# CW340_STATUS_LEDs.net
KiCad netlist of a schematic drawn in Altium Designer
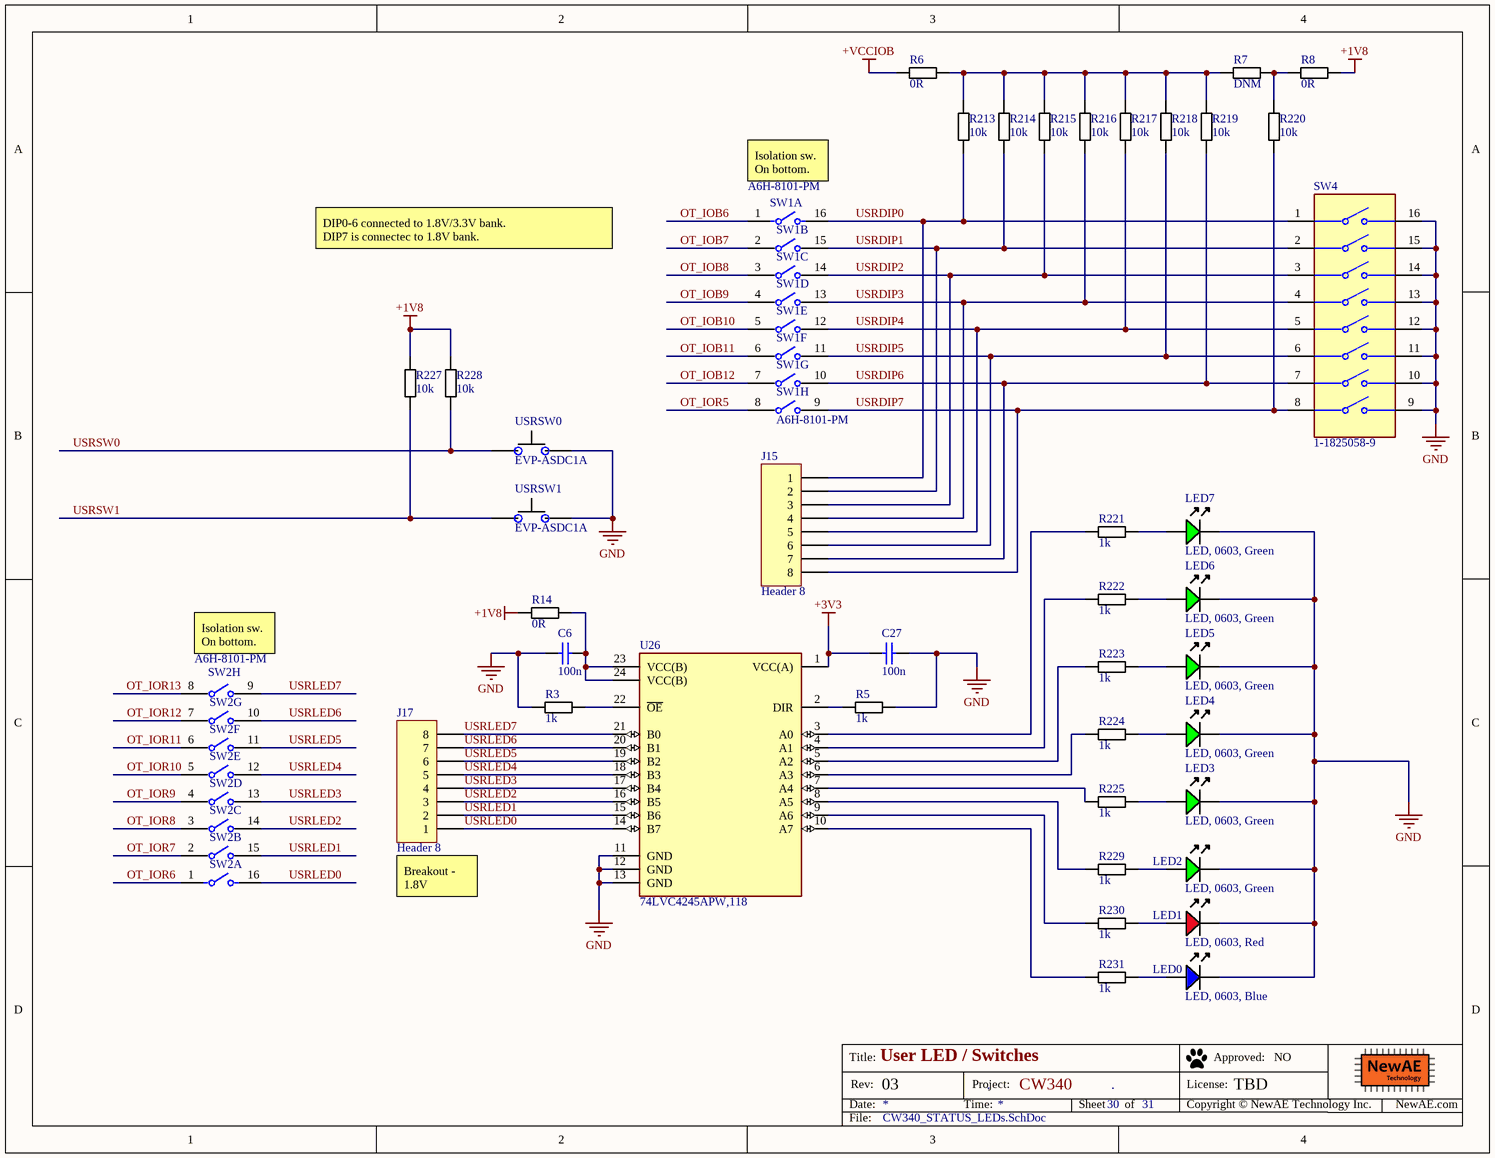
[diagram p0: CW340_STATUS_LEDs.SchDoc]

(export (version "E")
  (design (tool "Eeschema 10.0.6"))
  (components
    (comp (ref "C6")
      (value "100n")
      (footprint "CAPC0402_M")
      (description "100n, 0402")
      (fields (field (name "PART NUMBER") "CCHIP-100n-0402"))
      (libsource (lib "NewAE_AltiumLib") (part "CAP"))
    )
    (comp (ref "C27")
      (value "100n")
      (footprint "CAPC0402_M")
      (description "100n, 0402")
      (fields (field (name "PART NUMBER") "CCHIP-100n-0402"))
      (libsource (lib "NewAE_AltiumLib") (part "CAP"))
    )
    (comp (ref "J15")
      (value "Header 8")
      (footprint "HDR1X8")
      (description "Header, 8-Pin")
      (fields (field (name "PUBLISHER") "Altium Limited"))
      (libsource (lib "Miscellaneous Connectors") (part "Header 8"))
    )
    (comp (ref "J17")
      (value "Header 8")
      (footprint "HDR1X8")
      (description "Header, 8-Pin")
      (fields (field (name "PUBLISHER") "Altium Limited"))
      (libsource (lib "") (part "Header 8_1"))
    )
    (comp (ref "LED0")
      (value "LED, 0603, Blue")
      (footprint "LED-0603-BLUE")
      (description "Chip LED, Blue")
      (fields (field (name "PART NUMBER") "LEDCHIP_0603_BLUE"))
      (libsource (lib "NewAE_AltiumLib") (part "LED_BLUE"))
    )
    (comp (ref "LED1")
      (value "LED, 0603, Red")
      (footprint "LED-0603-RED")
      (description "Chip LED, Red")
      (fields (field (name "PART NUMBER") "LEDCHIP_0603_RED"))
      (libsource (lib "NewAE_AltiumLib") (part "LED_RED"))
    )
    (comp (ref "LED2")
      (value "LED, 0603, Green")
      (footprint "LED-0603-GREEN")
      (description "Chip LED, Green")
      (fields (field (name "PART NUMBER") "LEDCHIP_0603_GREEN"))
      (libsource (lib "NewAE_AltiumLib") (part "LED_GREEN"))
    )
    (comp (ref "LED3")
      (value "LED, 0603, Green")
      (footprint "LED-0603-GREEN")
      (description "Chip LED, Green")
      (fields (field (name "PART NUMBER") "LEDCHIP_0603_GREEN"))
      (libsource (lib "NewAE_AltiumLib") (part "LED_GREEN"))
    )
    (comp (ref "LED4")
      (value "LED, 0603, Green")
      (footprint "LED-0603-GREEN")
      (description "Chip LED, Green")
      (fields (field (name "PART NUMBER") "LEDCHIP_0603_GREEN"))
      (libsource (lib "NewAE_AltiumLib") (part "LED_GREEN"))
    )
    (comp (ref "LED5")
      (value "LED, 0603, Green")
      (footprint "LED-0603-GREEN")
      (description "Chip LED, Green")
      (fields (field (name "PART NUMBER") "LEDCHIP_0603_GREEN"))
      (libsource (lib "NewAE_AltiumLib") (part "LED_GREEN"))
    )
    (comp (ref "LED6")
      (value "LED, 0603, Green")
      (footprint "LED-0603-GREEN")
      (description "Chip LED, Green")
      (fields (field (name "PART NUMBER") "LEDCHIP_0603_GREEN"))
      (libsource (lib "NewAE_AltiumLib") (part "LED_GREEN"))
    )
    (comp (ref "LED7")
      (value "LED, 0603, Green")
      (footprint "LED-0603-GREEN")
      (description "Chip LED, Green")
      (fields (field (name "PART NUMBER") "LEDCHIP_0603_GREEN"))
      (libsource (lib "NewAE_AltiumLib") (part "LED_GREEN"))
    )
    (comp (ref "R3")
      (value "1k")
      (footprint "RESC1005X40N")
      (description "1k res, 0402, 1%, 1/16W")
      (fields (field (name "PART NUMBER") "RCHIP-1K-0402") (field (name "TOLERANCE") "1%"))
      (libsource (lib "NewAE_AltiumLib") (part "RES-EU"))
    )
    (comp (ref "R5")
      (value "1k")
      (footprint "RESC1005X40N")
      (description "1k res, 0402, 1%, 1/16W")
      (fields (field (name "PART NUMBER") "RCHIP-1K-0402") (field (name "TOLERANCE") "1%"))
      (libsource (lib "NewAE_AltiumLib") (part "RES-EU"))
    )
    (comp (ref "R6")
      (value "0R")
      (footprint "RESC1005X40N")
      (fields (field (name "PART NUMBER") "RCHIP-0R-0402"))
      (libsource (lib "NewAE_AltiumLib") (part "RES-EU"))
    )
    (comp (ref "R7")
      (value "DNM")
      (footprint "RESC1005X40N")
      (fields (field (name "PART NUMBER") "RCHIP-DNM-0402"))
      (libsource (lib "NewAE_AltiumLib") (part "RES-EU"))
    )
    (comp (ref "R8")
      (value "0R")
      (footprint "RESC1005X40N")
      (fields (field (name "PART NUMBER") "RCHIP-0R-0402"))
      (libsource (lib "NewAE_AltiumLib") (part "RES-EU"))
    )
    (comp (ref "R14")
      (value "0R")
      (footprint "RESC1005X40N")
      (fields (field (name "PART NUMBER") "RCHIP-0R-0402"))
      (libsource (lib "NewAE_AltiumLib") (part "RES-EU"))
    )
    (comp (ref "R213")
      (value "10k")
      (footprint "RESC1005X40N")
      (description "10k res, 0402, 1%, 1/16W")
      (fields (field (name "PART NUMBER") "RCHIP-10K-0402") (field (name "TOLERANCE") "1%"))
      (libsource (lib "") (part "RES-EU_1"))
    )
    (comp (ref "R214")
      (value "10k")
      (footprint "RESC1005X40N")
      (description "10k res, 0402, 1%, 1/16W")
      (fields (field (name "PART NUMBER") "RCHIP-10K-0402") (field (name "TOLERANCE") "1%"))
      (libsource (lib "") (part "RES-EU_1"))
    )
    (comp (ref "R215")
      (value "10k")
      (footprint "RESC1005X40N")
      (description "10k res, 0402, 1%, 1/16W")
      (fields (field (name "PART NUMBER") "RCHIP-10K-0402") (field (name "TOLERANCE") "1%"))
      (libsource (lib "") (part "RES-EU_1"))
    )
    (comp (ref "R216")
      (value "10k")
      (footprint "RESC1005X40N")
      (description "10k res, 0402, 1%, 1/16W")
      (fields (field (name "PART NUMBER") "RCHIP-10K-0402") (field (name "TOLERANCE") "1%"))
      (libsource (lib "") (part "RES-EU_1"))
    )
    (comp (ref "R217")
      (value "10k")
      (footprint "RESC1005X40N")
      (description "10k res, 0402, 1%, 1/16W")
      (fields (field (name "PART NUMBER") "RCHIP-10K-0402") (field (name "TOLERANCE") "1%"))
      (libsource (lib "") (part "RES-EU_1"))
    )
    (comp (ref "R218")
      (value "10k")
      (footprint "RESC1005X40N")
      (description "10k res, 0402, 1%, 1/16W")
      (fields (field (name "PART NUMBER") "RCHIP-10K-0402") (field (name "TOLERANCE") "1%"))
      (libsource (lib "") (part "RES-EU_1"))
    )
    (comp (ref "R219")
      (value "10k")
      (footprint "RESC1005X40N")
      (description "10k res, 0402, 1%, 1/16W")
      (fields (field (name "PART NUMBER") "RCHIP-10K-0402") (field (name "TOLERANCE") "1%"))
      (libsource (lib "") (part "RES-EU_1"))
    )
    (comp (ref "R220")
      (value "10k")
      (footprint "RESC1005X40N")
      (description "10k res, 0402, 1%, 1/16W")
      (fields (field (name "PART NUMBER") "RCHIP-10K-0402") (field (name "TOLERANCE") "1%"))
      (libsource (lib "") (part "RES-EU_1"))
    )
    (comp (ref "R221")
      (value "1k")
      (footprint "RESC1005X40N")
      (description "1k res, 0402, 1%, 1/16W")
      (fields (field (name "PART NUMBER") "RCHIP-1K-0402") (field (name "TOLERANCE") "1%"))
      (libsource (lib "NewAE_AltiumLib") (part "RES-EU"))
    )
    (comp (ref "R222")
      (value "1k")
      (footprint "RESC1005X40N")
      (description "1k res, 0402, 1%, 1/16W")
      (fields (field (name "PART NUMBER") "RCHIP-1K-0402") (field (name "TOLERANCE") "1%"))
      (libsource (lib "NewAE_AltiumLib") (part "RES-EU"))
    )
    (comp (ref "R223")
      (value "1k")
      (footprint "RESC1005X40N")
      (description "1k res, 0402, 1%, 1/16W")
      (fields (field (name "PART NUMBER") "RCHIP-1K-0402") (field (name "TOLERANCE") "1%"))
      (libsource (lib "NewAE_AltiumLib") (part "RES-EU"))
    )
    (comp (ref "R224")
      (value "1k")
      (footprint "RESC1005X40N")
      (description "1k res, 0402, 1%, 1/16W")
      (fields (field (name "PART NUMBER") "RCHIP-1K-0402") (field (name "TOLERANCE") "1%"))
      (libsource (lib "NewAE_AltiumLib") (part "RES-EU"))
    )
    (comp (ref "R225")
      (value "1k")
      (footprint "RESC1005X40N")
      (description "1k res, 0402, 1%, 1/16W")
      (fields (field (name "PART NUMBER") "RCHIP-1K-0402") (field (name "TOLERANCE") "1%"))
      (libsource (lib "NewAE_AltiumLib") (part "RES-EU"))
    )
    (comp (ref "R227")
      (value "10k")
      (footprint "RESC1005X40N")
      (description "10k res, 0402, 1%, 1/16W")
      (fields (field (name "PART NUMBER") "RCHIP-10K-0402") (field (name "TOLERANCE") "1%"))
      (libsource (lib "") (part "RES-EU_1"))
    )
    (comp (ref "R228")
      (value "10k")
      (footprint "RESC1005X40N")
      (description "10k res, 0402, 1%, 1/16W")
      (fields (field (name "PART NUMBER") "RCHIP-10K-0402") (field (name "TOLERANCE") "1%"))
      (libsource (lib "") (part "RES-EU_1"))
    )
    (comp (ref "R229")
      (value "1k")
      (footprint "RESC1005X40N")
      (description "1k res, 0402, 1%, 1/16W")
      (fields (field (name "PART NUMBER") "RCHIP-1K-0402") (field (name "TOLERANCE") "1%"))
      (libsource (lib "NewAE_AltiumLib") (part "RES-EU"))
    )
    (comp (ref "R230")
      (value "1k")
      (footprint "RESC1005X40N")
      (description "1k res, 0402, 1%, 1/16W")
      (fields (field (name "PART NUMBER") "RCHIP-1K-0402") (field (name "TOLERANCE") "1%"))
      (libsource (lib "NewAE_AltiumLib") (part "RES-EU"))
    )
    (comp (ref "R231")
      (value "1k")
      (footprint "RESC1005X40N")
      (description "1k res, 0402, 1%, 1/16W")
      (fields (field (name "PART NUMBER") "RCHIP-1K-0402") (field (name "TOLERANCE") "1%"))
      (libsource (lib "NewAE_AltiumLib") (part "RES-EU"))
    )
    (comp (ref "SW1")
      (value "A6H-8101-PM")
      (footprint "FP-A6H-8101-PM-MFG")
      (description "SWITCH SLIDE DIP SPST 25MA 24V")
      (libsource (lib "Altium Content Vault") (part "b1c630a2f26d6f55c46b66680387f8a"))
    )
    (comp (ref "SW2")
      (value "A6H-8101-PM")
      (footprint "FP-A6H-8101-PM-MFG")
      (description "SWITCH SLIDE DIP SPST 25MA 24V")
      (libsource (lib "Altium Content Vault") (part "b1c630a2f26d6f55c46b66680387f8a"))
    )
    (comp (ref "SW4")
      (value "1-1825058-9")
      (footprint "FP-1-1825058-9-MFG")
      (description "SWITCH SLIDE DIP SPST 100MA 24V")
      (fields
        (field (name "MANUFACTURER") "TE Connectivity")
        (field (name "OCTOPART") "https://octopart.com/1-1825058-9-te+connectivity-46507285")
      )
      (libsource (lib "Altium Content Vault") (part "88b473189f0daa5e8e83a09a3141fee"))
    )
    (comp (ref "U26")
      (value "74LVC4245APW,118")
      (footprint "FP-SOT355-1-MFG")
      (description "IC TRNSLTR BIDIRECTIONAL 24TSSOP")
      (libsource (lib "Altium Content Vault") (part "891e07fab61dc967ea688c1a07de794"))
    )
    (comp (ref "USRSW0")
      (value "EVP-ASDC1A")
      (footprint "EVPAS")
      (description "Pushbutton, SMD, 2.5NM force, NO")
      (libsource (lib "NewAE_AltiumLib") (part "SW_PB_NO_2PIN"))
    )
    (comp (ref "USRSW1")
      (value "EVP-ASDC1A")
      (footprint "EVPAS")
      (description "Pushbutton, SMD, 2.5NM force, NO")
      (libsource (lib "NewAE_AltiumLib") (part "SW_PB_NO_2PIN"))
    )
  )
  (nets
    (net (code "1") (name "+1V8") (class "Default")
      (node (ref "R14") (pin "1") (pinfunction "1_1") (pintype "passive"))
      (node (ref "R227") (pin "1") (pinfunction "1_1") (pintype "passive"))
      (node (ref "R228") (pin "1") (pinfunction "1_1") (pintype "passive"))
      (node (ref "R8") (pin "2") (pinfunction "2_2") (pintype "passive"))
    )
    (net (code "2") (name "+3V3") (class "Default")
      (node (ref "C27") (pin "1") (pinfunction "1_1") (pintype "passive"))
      (node (ref "U26") (pin "1") (pinfunction "VCC(A)_1") (pintype "power_in"))
    )
    (net (code "3") (name "+VCCIOB") (class "Default")
      (node (ref "R6") (pin "1") (pinfunction "1_1") (pintype "passive"))
    )
    (net (code "4") (name "/OT_IOB6") (class "Default")
      (node (ref "SW1") (pin "1") (pinfunction "1_1") (pintype "passive"))
    )
    (net (code "5") (name "/OT_IOB7") (class "Default")
      (node (ref "SW1") (pin "2") (pinfunction "2_2") (pintype "passive"))
    )
    (net (code "6") (name "/OT_IOB8") (class "Default")
      (node (ref "SW1") (pin "3") (pinfunction "3_3") (pintype "passive"))
    )
    (net (code "7") (name "/OT_IOB9") (class "Default")
      (node (ref "SW1") (pin "4") (pinfunction "4_4") (pintype "passive"))
    )
    (net (code "8") (name "/OT_IOB10") (class "Default")
      (node (ref "SW1") (pin "5") (pinfunction "5_5") (pintype "passive"))
    )
    (net (code "9") (name "/OT_IOB11") (class "Default")
      (node (ref "SW1") (pin "6") (pinfunction "6_6") (pintype "passive"))
    )
    (net (code "10") (name "/OT_IOB12") (class "Default")
      (node (ref "SW1") (pin "7") (pinfunction "7_7") (pintype "passive"))
    )
    (net (code "11") (name "/OT_IOR5") (class "Default")
      (node (ref "SW1") (pin "8") (pinfunction "8_8") (pintype "passive"))
    )
    (net (code "12") (name "/OT_IOR6") (class "Default")
      (node (ref "SW2") (pin "1") (pinfunction "1_1") (pintype "passive"))
    )
    (net (code "13") (name "/OT_IOR7") (class "Default")
      (node (ref "SW2") (pin "2") (pinfunction "2_2") (pintype "passive"))
    )
    (net (code "14") (name "/OT_IOR8") (class "Default")
      (node (ref "SW2") (pin "3") (pinfunction "3_3") (pintype "passive"))
    )
    (net (code "15") (name "/OT_IOR9") (class "Default")
      (node (ref "SW2") (pin "4") (pinfunction "4_4") (pintype "passive"))
    )
    (net (code "16") (name "/OT_IOR10") (class "Default")
      (node (ref "SW2") (pin "5") (pinfunction "5_5") (pintype "passive"))
    )
    (net (code "17") (name "/OT_IOR11") (class "Default")
      (node (ref "SW2") (pin "6") (pinfunction "6_6") (pintype "passive"))
    )
    (net (code "18") (name "/OT_IOR12") (class "Default")
      (node (ref "SW2") (pin "7") (pinfunction "7_7") (pintype "passive"))
    )
    (net (code "19") (name "/OT_IOR13") (class "Default")
      (node (ref "SW2") (pin "8") (pinfunction "8_8") (pintype "passive"))
    )
    (net (code "20") (name "/USRDIP0") (class "Default")
      (node (ref "J15") (pin "1") (pinfunction "1_1") (pintype "passive"))
      (node (ref "R213") (pin "2") (pinfunction "2_2") (pintype "passive"))
      (node (ref "SW1") (pin "16") (pinfunction "16_16") (pintype "passive"))
      (node (ref "SW4") (pin "1") (pinfunction "1_1") (pintype "passive"))
    )
    (net (code "21") (name "/USRDIP1") (class "Default")
      (node (ref "J15") (pin "2") (pinfunction "2_2") (pintype "passive"))
      (node (ref "R214") (pin "2") (pinfunction "2_2") (pintype "passive"))
      (node (ref "SW1") (pin "15") (pinfunction "15_15") (pintype "passive"))
      (node (ref "SW4") (pin "2") (pinfunction "2_2") (pintype "passive"))
    )
    (net (code "22") (name "/USRDIP2") (class "Default")
      (node (ref "J15") (pin "3") (pinfunction "3_3") (pintype "passive"))
      (node (ref "R215") (pin "2") (pinfunction "2_2") (pintype "passive"))
      (node (ref "SW1") (pin "14") (pinfunction "14_14") (pintype "passive"))
      (node (ref "SW4") (pin "3") (pinfunction "3_3") (pintype "passive"))
    )
    (net (code "23") (name "/USRDIP3") (class "Default")
      (node (ref "J15") (pin "4") (pinfunction "4_4") (pintype "passive"))
      (node (ref "R216") (pin "2") (pinfunction "2_2") (pintype "passive"))
      (node (ref "SW1") (pin "13") (pinfunction "13_13") (pintype "passive"))
      (node (ref "SW4") (pin "4") (pinfunction "4_4") (pintype "passive"))
    )
    (net (code "24") (name "/USRDIP4") (class "Default")
      (node (ref "J15") (pin "5") (pinfunction "5_5") (pintype "passive"))
      (node (ref "R217") (pin "2") (pinfunction "2_2") (pintype "passive"))
      (node (ref "SW1") (pin "12") (pinfunction "12_12") (pintype "passive"))
      (node (ref "SW4") (pin "5") (pinfunction "5_5") (pintype "passive"))
    )
    (net (code "25") (name "/USRDIP5") (class "Default")
      (node (ref "J15") (pin "6") (pinfunction "6_6") (pintype "passive"))
      (node (ref "R218") (pin "2") (pinfunction "2_2") (pintype "passive"))
      (node (ref "SW1") (pin "11") (pinfunction "11_11") (pintype "passive"))
      (node (ref "SW4") (pin "6") (pinfunction "6_6") (pintype "passive"))
    )
    (net (code "26") (name "/USRDIP6") (class "Default")
      (node (ref "J15") (pin "7") (pinfunction "7_7") (pintype "passive"))
      (node (ref "R219") (pin "2") (pinfunction "2_2") (pintype "passive"))
      (node (ref "SW1") (pin "10") (pinfunction "10_10") (pintype "passive"))
      (node (ref "SW4") (pin "7") (pinfunction "7_7") (pintype "passive"))
    )
    (net (code "27") (name "/USRDIP7") (class "Default")
      (node (ref "J15") (pin "8") (pinfunction "8_8") (pintype "passive"))
      (node (ref "R220") (pin "2") (pinfunction "2_2") (pintype "passive"))
      (node (ref "SW1") (pin "9") (pinfunction "9_9") (pintype "passive"))
      (node (ref "SW4") (pin "8") (pinfunction "8_8") (pintype "passive"))
    )
    (net (code "28") (name "/USRLED0") (class "Default")
      (node (ref "J17") (pin "1") (pinfunction "1_1") (pintype "passive"))
      (node (ref "SW2") (pin "16") (pinfunction "16_16") (pintype "passive"))
      (node (ref "U26") (pin "14") (pinfunction "B7_14") (pintype "bidirectional"))
    )
    (net (code "29") (name "/USRLED1") (class "Default")
      (node (ref "J17") (pin "2") (pinfunction "2_2") (pintype "passive"))
      (node (ref "SW2") (pin "15") (pinfunction "15_15") (pintype "passive"))
      (node (ref "U26") (pin "15") (pinfunction "B6_15") (pintype "bidirectional"))
    )
    (net (code "30") (name "/USRLED2") (class "Default")
      (node (ref "J17") (pin "3") (pinfunction "3_3") (pintype "passive"))
      (node (ref "SW2") (pin "14") (pinfunction "14_14") (pintype "passive"))
      (node (ref "U26") (pin "16") (pinfunction "B5_16") (pintype "bidirectional"))
    )
    (net (code "31") (name "/USRLED3") (class "Default")
      (node (ref "J17") (pin "4") (pinfunction "4_4") (pintype "passive"))
      (node (ref "SW2") (pin "13") (pinfunction "13_13") (pintype "passive"))
      (node (ref "U26") (pin "17") (pinfunction "B4_17") (pintype "bidirectional"))
    )
    (net (code "32") (name "/USRLED4") (class "Default")
      (node (ref "J17") (pin "5") (pinfunction "5_5") (pintype "passive"))
      (node (ref "SW2") (pin "12") (pinfunction "12_12") (pintype "passive"))
      (node (ref "U26") (pin "18") (pinfunction "B3_18") (pintype "bidirectional"))
    )
    (net (code "33") (name "/USRLED5") (class "Default")
      (node (ref "J17") (pin "6") (pinfunction "6_6") (pintype "passive"))
      (node (ref "SW2") (pin "11") (pinfunction "11_11") (pintype "passive"))
      (node (ref "U26") (pin "19") (pinfunction "B2_19") (pintype "bidirectional"))
    )
    (net (code "34") (name "/USRLED6") (class "Default")
      (node (ref "J17") (pin "7") (pinfunction "7_7") (pintype "passive"))
      (node (ref "SW2") (pin "10") (pinfunction "10_10") (pintype "passive"))
      (node (ref "U26") (pin "20") (pinfunction "B1_20") (pintype "bidirectional"))
    )
    (net (code "35") (name "/USRLED7") (class "Default")
      (node (ref "J17") (pin "8") (pinfunction "8_8") (pintype "passive"))
      (node (ref "SW2") (pin "9") (pinfunction "9_9") (pintype "passive"))
      (node (ref "U26") (pin "21") (pinfunction "B0_21") (pintype "bidirectional"))
    )
    (net (code "36") (name "/USRSW0") (class "Default")
      (node (ref "R228") (pin "2") (pinfunction "2_2") (pintype "passive"))
      (node (ref "USRSW0") (pin "1") (pinfunction "IN_1") (pintype "passive"))
    )
    (net (code "37") (name "/USRSW1") (class "Default")
      (node (ref "R227") (pin "2") (pinfunction "2_2") (pintype "passive"))
      (node (ref "USRSW1") (pin "1") (pinfunction "IN_1") (pintype "passive"))
    )
    (net (code "38") (name "GND") (class "Default")
      (node (ref "C27") (pin "2") (pinfunction "2_2") (pintype "passive"))
      (node (ref "C6") (pin "1") (pinfunction "1_1") (pintype "passive"))
      (node (ref "LED0") (pin "K") (pinfunction "K_K") (pintype "passive"))
      (node (ref "LED1") (pin "K") (pinfunction "K_K") (pintype "passive"))
      (node (ref "LED2") (pin "K") (pinfunction "K_K") (pintype "passive"))
      (node (ref "LED3") (pin "K") (pinfunction "K_K") (pintype "passive"))
      (node (ref "LED4") (pin "K") (pinfunction "K_K") (pintype "passive"))
      (node (ref "LED5") (pin "K") (pinfunction "K_K") (pintype "passive"))
      (node (ref "LED6") (pin "K") (pinfunction "K_K") (pintype "passive"))
      (node (ref "LED7") (pin "K") (pinfunction "K_K") (pintype "passive"))
      (node (ref "R3") (pin "1") (pinfunction "1_1") (pintype "passive"))
      (node (ref "R5") (pin "2") (pinfunction "2_2") (pintype "passive"))
      (node (ref "SW4") (pin "10") (pinfunction "10_10") (pintype "passive"))
      (node (ref "SW4") (pin "11") (pinfunction "11_11") (pintype "passive"))
      (node (ref "SW4") (pin "12") (pinfunction "12_12") (pintype "passive"))
      (node (ref "SW4") (pin "13") (pinfunction "13_13") (pintype "passive"))
      (node (ref "SW4") (pin "14") (pinfunction "14_14") (pintype "passive"))
      (node (ref "SW4") (pin "15") (pinfunction "15_15") (pintype "passive"))
      (node (ref "SW4") (pin "16") (pinfunction "16_16") (pintype "passive"))
      (node (ref "SW4") (pin "9") (pinfunction "9_9") (pintype "passive"))
      (node (ref "U26") (pin "11") (pinfunction "GND_11") (pintype "power_in"))
      (node (ref "U26") (pin "12") (pinfunction "GND_12") (pintype "power_in"))
      (node (ref "U26") (pin "13") (pinfunction "GND_13") (pintype "power_in"))
      (node (ref "USRSW0") (pin "2") (pinfunction "IN_2") (pintype "passive"))
      (node (ref "USRSW1") (pin "2") (pinfunction "IN_2") (pintype "passive"))
    )
    (net (code "39") (name "Net-(C6-Pad2)") (class "Default")
      (node (ref "C6") (pin "2") (pinfunction "2_2") (pintype "passive"))
      (node (ref "R14") (pin "2") (pinfunction "2_2") (pintype "passive"))
      (node (ref "U26") (pin "23") (pinfunction "VCC(B)_23") (pintype "power_in"))
      (node (ref "U26") (pin "24") (pinfunction "VCC(B)_24") (pintype "power_in"))
    )
    (net (code "40") (name "Net-(LED0-PadA)") (class "Default")
      (node (ref "LED0") (pin "A") (pinfunction "A_A") (pintype "passive"))
      (node (ref "R231") (pin "2") (pinfunction "2_2") (pintype "passive"))
    )
    (net (code "41") (name "Net-(LED1-PadA)") (class "Default")
      (node (ref "LED1") (pin "A") (pinfunction "A_A") (pintype "passive"))
      (node (ref "R230") (pin "2") (pinfunction "2_2") (pintype "passive"))
    )
    (net (code "42") (name "Net-(LED2-PadA)") (class "Default")
      (node (ref "LED2") (pin "A") (pinfunction "A_A") (pintype "passive"))
      (node (ref "R229") (pin "2") (pinfunction "2_2") (pintype "passive"))
    )
    (net (code "43") (name "Net-(LED3-PadA)") (class "Default")
      (node (ref "LED3") (pin "A") (pinfunction "A_A") (pintype "passive"))
      (node (ref "R225") (pin "2") (pinfunction "2_2") (pintype "passive"))
    )
    (net (code "44") (name "Net-(LED4-PadA)") (class "Default")
      (node (ref "LED4") (pin "A") (pinfunction "A_A") (pintype "passive"))
      (node (ref "R224") (pin "2") (pinfunction "2_2") (pintype "passive"))
    )
    (net (code "45") (name "Net-(LED5-PadA)") (class "Default")
      (node (ref "LED5") (pin "A") (pinfunction "A_A") (pintype "passive"))
      (node (ref "R223") (pin "2") (pinfunction "2_2") (pintype "passive"))
    )
    (net (code "46") (name "Net-(LED6-PadA)") (class "Default")
      (node (ref "LED6") (pin "A") (pinfunction "A_A") (pintype "passive"))
      (node (ref "R222") (pin "2") (pinfunction "2_2") (pintype "passive"))
    )
    (net (code "47") (name "Net-(LED7-PadA)") (class "Default")
      (node (ref "LED7") (pin "A") (pinfunction "A_A") (pintype "passive"))
      (node (ref "R221") (pin "2") (pinfunction "2_2") (pintype "passive"))
    )
    (net (code "48") (name "Net-(R213-Pad1)") (class "Default")
      (node (ref "R213") (pin "1") (pinfunction "1_1") (pintype "passive"))
      (node (ref "R214") (pin "1") (pinfunction "1_1") (pintype "passive"))
      (node (ref "R215") (pin "1") (pinfunction "1_1") (pintype "passive"))
      (node (ref "R216") (pin "1") (pinfunction "1_1") (pintype "passive"))
      (node (ref "R217") (pin "1") (pinfunction "1_1") (pintype "passive"))
      (node (ref "R218") (pin "1") (pinfunction "1_1") (pintype "passive"))
      (node (ref "R219") (pin "1") (pinfunction "1_1") (pintype "passive"))
      (node (ref "R6") (pin "2") (pinfunction "2_2") (pintype "passive"))
      (node (ref "R7") (pin "1") (pinfunction "1_1") (pintype "passive"))
    )
    (net (code "49") (name "Net-(R220-Pad1)") (class "Default")
      (node (ref "R220") (pin "1") (pinfunction "1_1") (pintype "passive"))
      (node (ref "R7") (pin "2") (pinfunction "2_2") (pintype "passive"))
      (node (ref "R8") (pin "1") (pinfunction "1_1") (pintype "passive"))
    )
    (net (code "50") (name "Net-(U26-A0)") (class "Default")
      (node (ref "R221") (pin "1") (pinfunction "1_1") (pintype "passive"))
      (node (ref "U26") (pin "3") (pinfunction "A0_3") (pintype "bidirectional"))
    )
    (net (code "51") (name "Net-(U26-A1)") (class "Default")
      (node (ref "R222") (pin "1") (pinfunction "1_1") (pintype "passive"))
      (node (ref "U26") (pin "4") (pinfunction "A1_4") (pintype "bidirectional"))
    )
    (net (code "52") (name "Net-(U26-A2)") (class "Default")
      (node (ref "R223") (pin "1") (pinfunction "1_1") (pintype "passive"))
      (node (ref "U26") (pin "5") (pinfunction "A2_5") (pintype "bidirectional"))
    )
    (net (code "53") (name "Net-(U26-A3)") (class "Default")
      (node (ref "R224") (pin "1") (pinfunction "1_1") (pintype "passive"))
      (node (ref "U26") (pin "6") (pinfunction "A3_6") (pintype "bidirectional"))
    )
    (net (code "54") (name "Net-(U26-A4)") (class "Default")
      (node (ref "R225") (pin "1") (pinfunction "1_1") (pintype "passive"))
      (node (ref "U26") (pin "7") (pinfunction "A4_7") (pintype "bidirectional"))
    )
    (net (code "55") (name "Net-(U26-A5)") (class "Default")
      (node (ref "R229") (pin "1") (pinfunction "1_1") (pintype "passive"))
      (node (ref "U26") (pin "8") (pinfunction "A5_8") (pintype "bidirectional"))
    )
    (net (code "56") (name "Net-(U26-A6)") (class "Default")
      (node (ref "R230") (pin "1") (pinfunction "1_1") (pintype "passive"))
      (node (ref "U26") (pin "9") (pinfunction "A6_9") (pintype "bidirectional"))
    )
    (net (code "57") (name "Net-(U26-A7)") (class "Default")
      (node (ref "R231") (pin "1") (pinfunction "1_1") (pintype "passive"))
      (node (ref "U26") (pin "10") (pinfunction "A7_10") (pintype "bidirectional"))
    )
    (net (code "58") (name "Net-(U26-DIR)") (class "Default")
      (node (ref "R5") (pin "1") (pinfunction "1_1") (pintype "passive"))
      (node (ref "U26") (pin "2") (pinfunction "DIR_2") (pintype "passive"))
    )
    (net (code "59") (name "Net-(U26-~{OE})") (class "Default")
      (node (ref "R3") (pin "2") (pinfunction "2_2") (pintype "passive"))
      (node (ref "U26") (pin "22") (pinfunction "~{OE}_22") (pintype "passive"))
    )
  )
)
